# M7075X.net
KiCad netlist of a schematic drawn in EAGLE
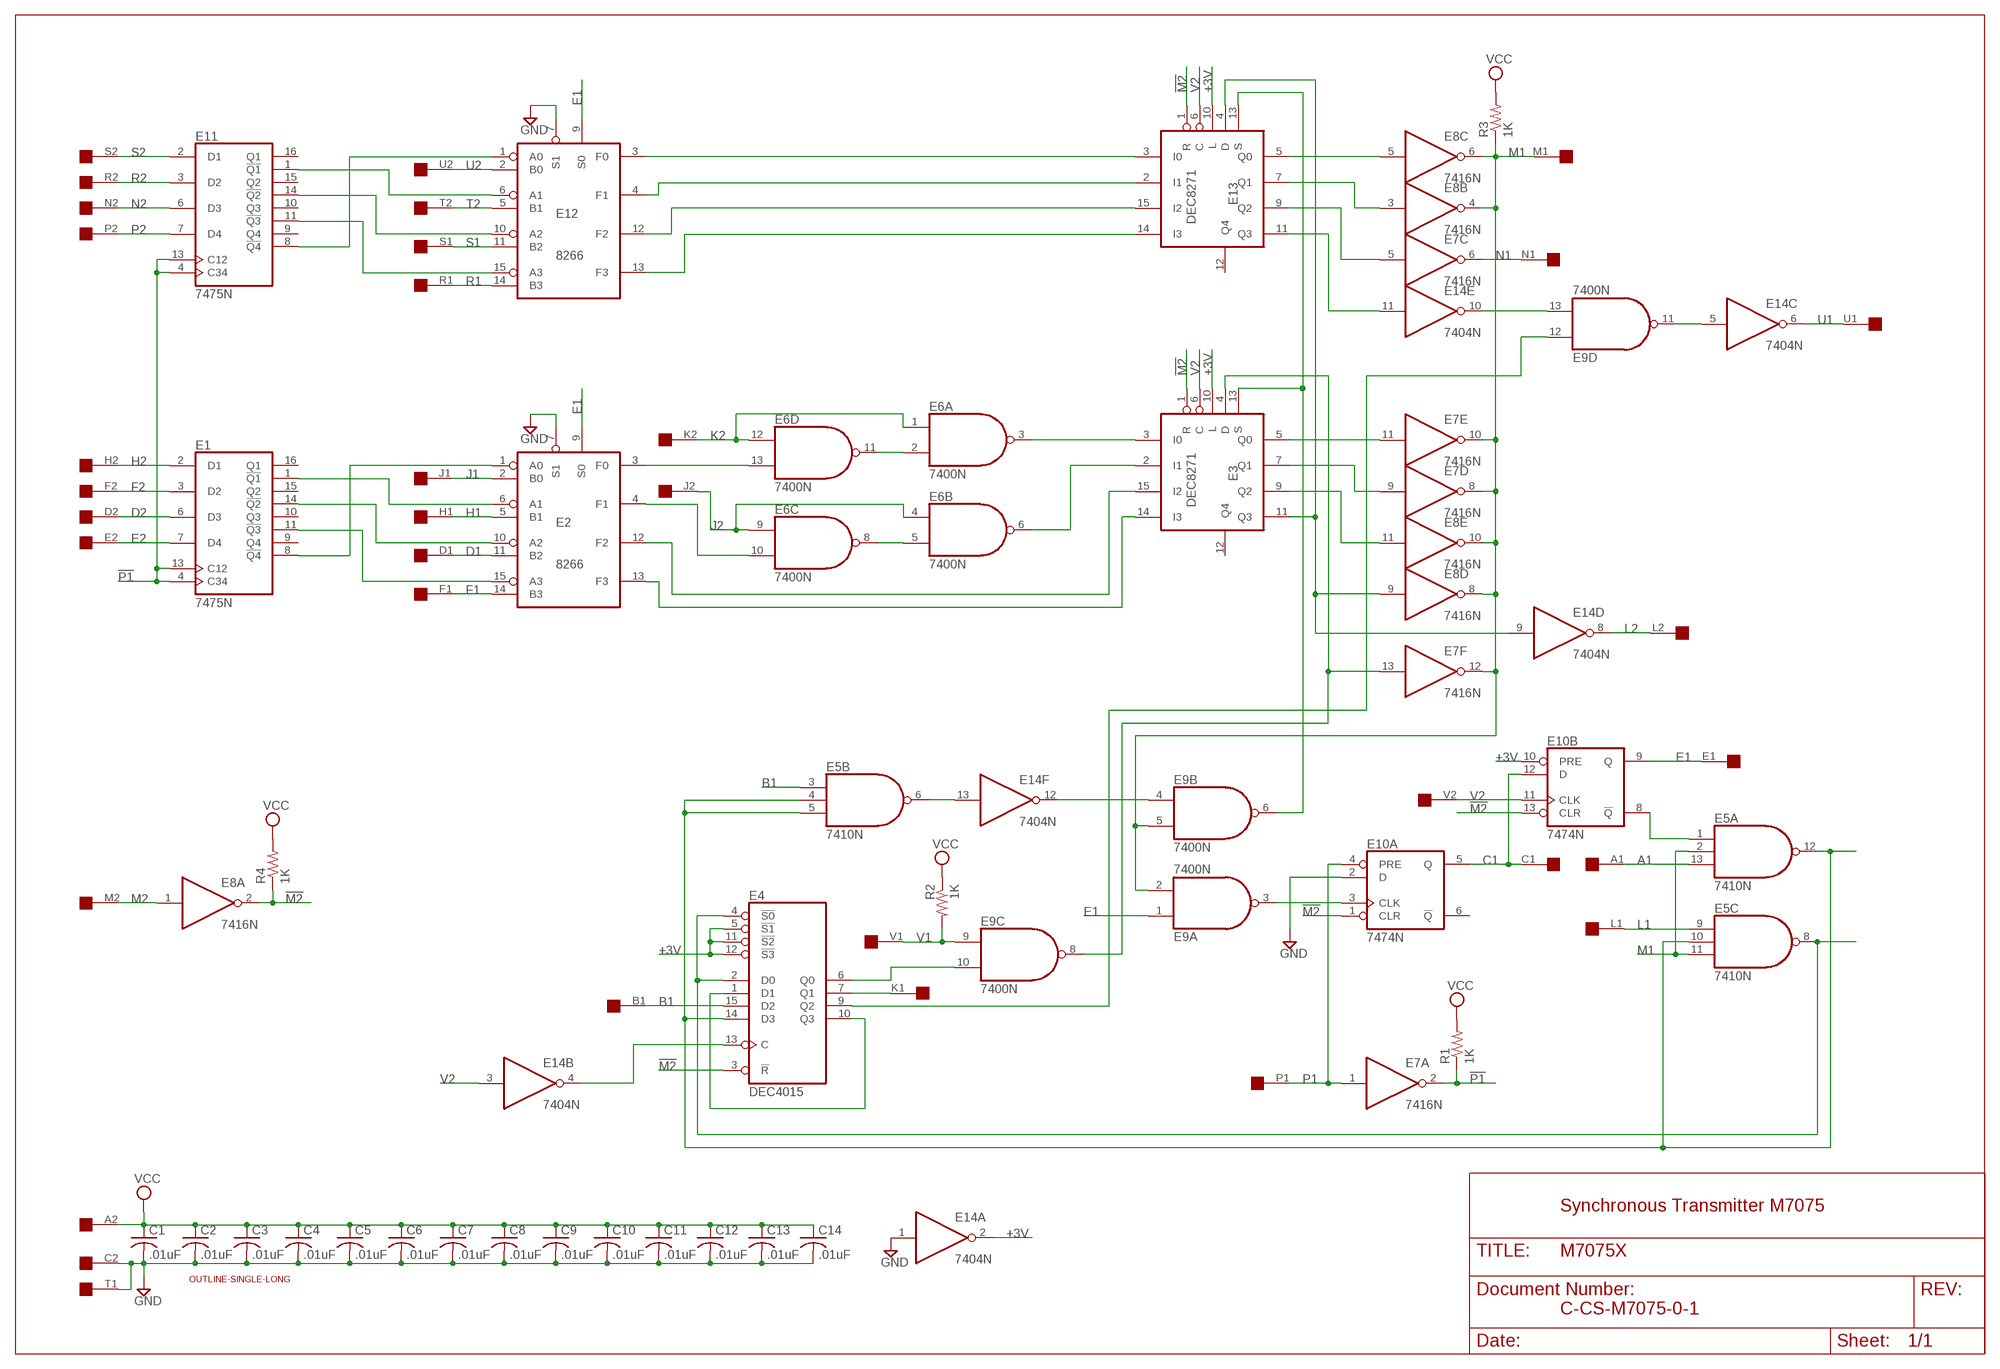
[diagram p0: schematic, sheet 1]

(export (version "E")
  (design (tool "Eeschema 10.0.6"))
  (components
    (comp (ref "C1")
      (value ".01uF")
      (footprint "eagle-import:C050-025X075")
      (libsource (lib "eagle-import") (part "C-US050-025X075"))
    )
    (comp (ref "C2")
      (value ".01uF")
      (footprint "eagle-import:C050-025X075")
      (libsource (lib "eagle-import") (part "C-US050-025X075"))
    )
    (comp (ref "C3")
      (value ".01uF")
      (footprint "eagle-import:C050-025X075")
      (libsource (lib "eagle-import") (part "C-US050-025X075"))
    )
    (comp (ref "C4")
      (value ".01uF")
      (footprint "eagle-import:C050-025X075")
      (libsource (lib "eagle-import") (part "C-US050-025X075"))
    )
    (comp (ref "C5")
      (value ".01uF")
      (footprint "eagle-import:C050-025X075")
      (libsource (lib "eagle-import") (part "C-US050-025X075"))
    )
    (comp (ref "C6")
      (value ".01uF")
      (footprint "eagle-import:C050-025X075")
      (libsource (lib "eagle-import") (part "C-US050-025X075"))
    )
    (comp (ref "C7")
      (value ".01uF")
      (footprint "eagle-import:C050-025X075")
      (libsource (lib "eagle-import") (part "C-US050-025X075"))
    )
    (comp (ref "C8")
      (value ".01uF")
      (footprint "eagle-import:C050-025X075")
      (libsource (lib "eagle-import") (part "C-US050-025X075"))
    )
    (comp (ref "C9")
      (value ".01uF")
      (footprint "eagle-import:C050-025X075")
      (libsource (lib "eagle-import") (part "C-US050-025X075"))
    )
    (comp (ref "C10")
      (value ".01uF")
      (footprint "eagle-import:C050-025X075")
      (libsource (lib "eagle-import") (part "C-US050-025X075"))
    )
    (comp (ref "C11")
      (value ".01uF")
      (footprint "eagle-import:C050-025X075")
      (libsource (lib "eagle-import") (part "C-US050-025X075"))
    )
    (comp (ref "C12")
      (value ".01uF")
      (footprint "eagle-import:C050-025X075")
      (libsource (lib "eagle-import") (part "C-US050-025X075"))
    )
    (comp (ref "C13")
      (value ".01uF")
      (footprint "eagle-import:C050-025X075")
      (libsource (lib "eagle-import") (part "C-US050-025X075"))
    )
    (comp (ref "C14")
      (value ".01uF")
      (footprint "eagle-import:C050-025X075")
      (libsource (lib "eagle-import") (part "C-US050-025X075"))
    )
    (comp (ref "E1")
      (value "7475N")
      (footprint "eagle-import:DIL16")
      (libsource (lib "eagle-import") (part "7475N"))
    )
    (comp (ref "E2")
      (value "8266")
      (footprint "eagle-import:DIL16")
      (libsource (lib "eagle-import") (part "8266"))
    )
    (comp (ref "E3")
      (value "DEC8271")
      (footprint "eagle-import:DIL16")
      (libsource (lib "eagle-import") (part "DEC8271"))
    )
    (comp (ref "E4")
      (value "DEC4015")
      (footprint "eagle-import:DIL16")
      (libsource (lib "eagle-import") (part "DEC4015"))
    )
    (comp (ref "E5")
      (value "7410N")
      (footprint "eagle-import:DIL14")
      (libsource (lib "eagle-import") (part "7410N"))
    )
    (comp (ref "E6")
      (value "7400N")
      (footprint "eagle-import:DIL14")
      (libsource (lib "eagle-import") (part "7400N"))
    )
    (comp (ref "E7")
      (value "7416N")
      (footprint "eagle-import:DIL14")
      (libsource (lib "eagle-import") (part "7416N"))
    )
    (comp (ref "E8")
      (value "7416N")
      (footprint "eagle-import:DIL14")
      (libsource (lib "eagle-import") (part "7416N"))
    )
    (comp (ref "E9")
      (value "7400N")
      (footprint "eagle-import:DIL14")
      (libsource (lib "eagle-import") (part "7400N"))
    )
    (comp (ref "E10")
      (value "7474N")
      (footprint "eagle-import:DIL14")
      (libsource (lib "eagle-import") (part "7474NS"))
    )
    (comp (ref "E11")
      (value "7475N")
      (footprint "eagle-import:DIL16")
      (libsource (lib "eagle-import") (part "7475N"))
    )
    (comp (ref "E12")
      (value "8266")
      (footprint "eagle-import:DIL16")
      (libsource (lib "eagle-import") (part "8266"))
    )
    (comp (ref "E13")
      (value "DEC8271")
      (footprint "eagle-import:DIL16")
      (libsource (lib "eagle-import") (part "DEC8271"))
    )
    (comp (ref "E14")
      (value "7404N")
      (footprint "eagle-import:DIL14")
      (libsource (lib "eagle-import") (part "7404N"))
    )
    (comp (ref "R1")
      (value "1K")
      (footprint "eagle-import:0207_10")
      (libsource (lib "eagle-import") (part "R-US_0207/10"))
    )
    (comp (ref "R2")
      (value "1K")
      (footprint "eagle-import:0207_10")
      (libsource (lib "eagle-import") (part "R-US_0207/10"))
    )
    (comp (ref "R3")
      (value "1K")
      (footprint "eagle-import:0207_10")
      (libsource (lib "eagle-import") (part "R-US_0207/10"))
    )
    (comp (ref "R4")
      (value "1K")
      (footprint "eagle-import:0207_10")
      (libsource (lib "eagle-import") (part "R-US_0207/10"))
    )
    (comp (ref "U$1")
      (value "OUTLINE-SINGLE-LONG")
      (footprint "eagle-import:SINGLE-LONG")
      (libsource (lib "eagle-import") (part "OUTLINE-SINGLE-LONG"))
    )
    (comp (ref "U$2")
      (value "SINGLE")
      (footprint "eagle-import:EDGE-CON2")
      (libsource (lib "eagle-import") (part "SINGLE"))
    )
  )
  (nets
    (net (code "1") (name "/+3V") (class "Default")
      (node (ref "E10") (pin "10") (pinfunction "PRE_10") (pintype "input"))
      (node (ref "E13") (pin "10") (pinfunction "L_10") (pintype "input"))
      (node (ref "E14") (pin "2") (pinfunction "O_2") (pintype "output"))
      (node (ref "E3") (pin "10") (pinfunction "L_10") (pintype "input"))
      (node (ref "E4") (pin "11") (pinfunction "~{S2}_11") (pintype "input"))
      (node (ref "E4") (pin "12") (pinfunction "~{S3}_12") (pintype "input"))
      (node (ref "E4") (pin "5") (pinfunction "~{S1}_5") (pintype "input"))
    )
    (net (code "2") (name "/A1") (class "Default")
      (node (ref "E5") (pin "13") (pinfunction "I2_13") (pintype "input"))
      (node (ref "U$2") (pin "A1") (pinfunction "1_A1") (pintype "bidirectional"))
    )
    (net (code "3") (name "/B1") (class "Default")
      (node (ref "E4") (pin "15") (pinfunction "D2_15") (pintype "input"))
      (node (ref "E5") (pin "3") (pinfunction "I0_3") (pintype "input"))
      (node (ref "U$2") (pin "B1") (pinfunction "1_B1") (pintype "bidirectional"))
    )
    (net (code "4") (name "/C1") (class "Default")
      (node (ref "E10") (pin "12") (pinfunction "D_12") (pintype "input"))
      (node (ref "E10") (pin "5") (pinfunction "Q_5") (pintype "output"))
      (node (ref "U$2") (pin "C1") (pinfunction "1_C1") (pintype "bidirectional"))
    )
    (net (code "5") (name "/D1") (class "Default")
      (node (ref "E2") (pin "11") (pinfunction "B2_11") (pintype "input"))
      (node (ref "U$2") (pin "D1") (pinfunction "1_D1") (pintype "bidirectional"))
    )
    (net (code "6") (name "/D2") (class "Default")
      (node (ref "E1") (pin "6") (pinfunction "D3_6") (pintype "input"))
      (node (ref "U$2") (pin "D2") (pinfunction "1_D2") (pintype "bidirectional"))
    )
    (net (code "7") (name "/E1") (class "Default")
      (node (ref "E10") (pin "9") (pinfunction "Q_9") (pintype "output"))
      (node (ref "E12") (pin "9") (pinfunction "S0_9") (pintype "input"))
      (node (ref "E2") (pin "9") (pinfunction "S0_9") (pintype "input"))
      (node (ref "E9") (pin "1") (pinfunction "I0_1") (pintype "input"))
      (node (ref "U$2") (pin "E1") (pinfunction "1_E1") (pintype "bidirectional"))
    )
    (net (code "8") (name "/E2") (class "Default")
      (node (ref "E1") (pin "7") (pinfunction "D4_7") (pintype "input"))
      (node (ref "U$2") (pin "E2") (pinfunction "1_E2") (pintype "bidirectional"))
    )
    (net (code "9") (name "/F1") (class "Default")
      (node (ref "E2") (pin "14") (pinfunction "B3_14") (pintype "input"))
      (node (ref "U$2") (pin "F1") (pinfunction "1_F1") (pintype "bidirectional"))
    )
    (net (code "10") (name "/F2") (class "Default")
      (node (ref "E1") (pin "3") (pinfunction "D2_3") (pintype "input"))
      (node (ref "U$2") (pin "F2") (pinfunction "1_F2") (pintype "bidirectional"))
    )
    (net (code "11") (name "/H1") (class "Default")
      (node (ref "E2") (pin "5") (pinfunction "B1_5") (pintype "input"))
      (node (ref "U$2") (pin "H1") (pinfunction "1_H1") (pintype "bidirectional"))
    )
    (net (code "12") (name "/H2") (class "Default")
      (node (ref "E1") (pin "2") (pinfunction "D1_2") (pintype "input"))
      (node (ref "U$2") (pin "H2") (pinfunction "1_H2") (pintype "bidirectional"))
    )
    (net (code "13") (name "/J1") (class "Default")
      (node (ref "E2") (pin "2") (pinfunction "B0_2") (pintype "input"))
      (node (ref "U$2") (pin "J1") (pinfunction "1_J1") (pintype "bidirectional"))
    )
    (net (code "14") (name "/J2") (class "Default")
      (node (ref "E6") (pin "4") (pinfunction "I0_4") (pintype "input"))
      (node (ref "E6") (pin "9") (pinfunction "I0_9") (pintype "input"))
      (node (ref "U$2") (pin "J2") (pinfunction "1_J2") (pintype "bidirectional"))
    )
    (net (code "15") (name "/K2") (class "Default")
      (node (ref "E6") (pin "1") (pinfunction "I0_1") (pintype "input"))
      (node (ref "E6") (pin "12") (pinfunction "I0_12") (pintype "input"))
      (node (ref "U$2") (pin "K2") (pinfunction "1_K2") (pintype "bidirectional"))
    )
    (net (code "16") (name "/L1") (class "Default")
      (node (ref "E5") (pin "9") (pinfunction "I0_9") (pintype "input"))
      (node (ref "U$2") (pin "L1") (pinfunction "1_L1") (pintype "bidirectional"))
    )
    (net (code "17") (name "/L2") (class "Default")
      (node (ref "E14") (pin "8") (pinfunction "O_8") (pintype "output"))
      (node (ref "U$2") (pin "L2") (pinfunction "1_L2") (pintype "bidirectional"))
    )
    (net (code "18") (name "/M1") (class "Default")
      (node (ref "E5") (pin "11") (pinfunction "I2_11") (pintype "input"))
      (node (ref "E5") (pin "2") (pinfunction "I1_2") (pintype "input"))
      (node (ref "E7") (pin "10") (pinfunction "O_10") (pintype "open_collector"))
      (node (ref "E7") (pin "12") (pinfunction "O_12") (pintype "open_collector"))
      (node (ref "E7") (pin "8") (pinfunction "O_8") (pintype "open_collector"))
      (node (ref "E8") (pin "10") (pinfunction "O_10") (pintype "open_collector"))
      (node (ref "E8") (pin "4") (pinfunction "O_4") (pintype "open_collector"))
      (node (ref "E8") (pin "6") (pinfunction "O_6") (pintype "open_collector"))
      (node (ref "E8") (pin "8") (pinfunction "O_8") (pintype "open_collector"))
      (node (ref "E9") (pin "2") (pinfunction "I1_2") (pintype "input"))
      (node (ref "E9") (pin "5") (pinfunction "I1_5") (pintype "input"))
      (node (ref "R3") (pin "1") (pinfunction "1_1") (pintype "passive"))
      (node (ref "U$2") (pin "M1") (pinfunction "1_M1") (pintype "bidirectional"))
    )
    (net (code "19") (name "/M2") (class "Default")
      (node (ref "E8") (pin "1") (pinfunction "I_1") (pintype "input"))
      (node (ref "U$2") (pin "M2") (pinfunction "1_M2") (pintype "bidirectional"))
    )
    (net (code "20") (name "/N1") (class "Default")
      (node (ref "E7") (pin "6") (pinfunction "O_6") (pintype "open_collector"))
      (node (ref "U$2") (pin "N1") (pinfunction "1_N1") (pintype "bidirectional"))
    )
    (net (code "21") (name "/N2") (class "Default")
      (node (ref "E11") (pin "6") (pinfunction "D3_6") (pintype "input"))
      (node (ref "U$2") (pin "N2") (pinfunction "1_N2") (pintype "bidirectional"))
    )
    (net (code "22") (name "/P1") (class "Default")
      (node (ref "E10") (pin "4") (pinfunction "PRE_4") (pintype "input"))
      (node (ref "E7") (pin "1") (pinfunction "I_1") (pintype "input"))
      (node (ref "U$2") (pin "P1") (pinfunction "1_P1") (pintype "bidirectional"))
    )
    (net (code "23") (name "/P2") (class "Default")
      (node (ref "E11") (pin "7") (pinfunction "D4_7") (pintype "input"))
      (node (ref "U$2") (pin "P2") (pinfunction "1_P2") (pintype "bidirectional"))
    )
    (net (code "24") (name "/R1") (class "Default")
      (node (ref "E12") (pin "14") (pinfunction "B3_14") (pintype "input"))
      (node (ref "U$2") (pin "R1") (pinfunction "1_R1") (pintype "bidirectional"))
    )
    (net (code "25") (name "/R2") (class "Default")
      (node (ref "E11") (pin "3") (pinfunction "D2_3") (pintype "input"))
      (node (ref "U$2") (pin "R2") (pinfunction "1_R2") (pintype "bidirectional"))
    )
    (net (code "26") (name "/S1") (class "Default")
      (node (ref "E12") (pin "11") (pinfunction "B2_11") (pintype "input"))
      (node (ref "U$2") (pin "S1") (pinfunction "1_S1") (pintype "bidirectional"))
    )
    (net (code "27") (name "/S2") (class "Default")
      (node (ref "E11") (pin "2") (pinfunction "D1_2") (pintype "input"))
      (node (ref "U$2") (pin "S2") (pinfunction "1_S2") (pintype "bidirectional"))
    )
    (net (code "28") (name "/T2") (class "Default")
      (node (ref "E12") (pin "5") (pinfunction "B1_5") (pintype "input"))
      (node (ref "U$2") (pin "T2") (pinfunction "1_T2") (pintype "bidirectional"))
    )
    (net (code "29") (name "/U1") (class "Default")
      (node (ref "E14") (pin "6") (pinfunction "O_6") (pintype "output"))
      (node (ref "U$2") (pin "U1") (pinfunction "1_U1") (pintype "bidirectional"))
    )
    (net (code "30") (name "/U2") (class "Default")
      (node (ref "E12") (pin "2") (pinfunction "B0_2") (pintype "input"))
      (node (ref "U$2") (pin "U2") (pinfunction "1_U2") (pintype "bidirectional"))
    )
    (net (code "31") (name "/V1") (class "Default")
      (node (ref "E9") (pin "9") (pinfunction "I0_9") (pintype "input"))
      (node (ref "R2") (pin "2") (pinfunction "2_2") (pintype "passive"))
      (node (ref "U$2") (pin "V1") (pinfunction "1_V1") (pintype "bidirectional"))
    )
    (net (code "32") (name "/V2") (class "Default")
      (node (ref "E10") (pin "11") (pinfunction "CLK_11") (pintype "input"))
      (node (ref "E13") (pin "6") (pinfunction "C_6") (pintype "input"))
      (node (ref "E14") (pin "3") (pinfunction "I_3") (pintype "input"))
      (node (ref "E3") (pin "6") (pinfunction "C_6") (pintype "input"))
      (node (ref "U$2") (pin "V2") (pinfunction "1_V2") (pintype "bidirectional"))
    )
    (net (code "33") (name "/~{M2}") (class "Default")
      (node (ref "E10") (pin "1") (pinfunction "CLR_1") (pintype "input"))
      (node (ref "E10") (pin "13") (pinfunction "CLR_13") (pintype "input"))
      (node (ref "E13") (pin "1") (pinfunction "R_1") (pintype "input"))
      (node (ref "E3") (pin "1") (pinfunction "R_1") (pintype "input"))
      (node (ref "E4") (pin "3") (pinfunction "~{R}_3") (pintype "input"))
      (node (ref "E8") (pin "2") (pinfunction "O_2") (pintype "open_collector"))
      (node (ref "R4") (pin "1") (pinfunction "1_1") (pintype "passive"))
    )
    (net (code "34") (name "/~{P1}") (class "Default")
      (node (ref "E1") (pin "13") (pinfunction "C12_13") (pintype "input"))
      (node (ref "E1") (pin "4") (pinfunction "C34_4") (pintype "input"))
      (node (ref "E11") (pin "13") (pinfunction "C12_13") (pintype "input"))
      (node (ref "E11") (pin "4") (pinfunction "C34_4") (pintype "input"))
      (node (ref "E7") (pin "2") (pinfunction "O_2") (pintype "open_collector"))
      (node (ref "R1") (pin "1") (pinfunction "1_1") (pintype "passive"))
    )
    (net (code "35") (name "GND") (class "Default")
      (node (ref "C1") (pin "2") (pinfunction "2_2") (pintype "passive"))
      (node (ref "C10") (pin "2") (pinfunction "2_2") (pintype "passive"))
      (node (ref "C11") (pin "2") (pinfunction "2_2") (pintype "passive"))
      (node (ref "C12") (pin "2") (pinfunction "2_2") (pintype "passive"))
      (node (ref "C13") (pin "2") (pinfunction "2_2") (pintype "passive"))
      (node (ref "C14") (pin "2") (pinfunction "2_2") (pintype "passive"))
      (node (ref "C2") (pin "2") (pinfunction "2_2") (pintype "passive"))
      (node (ref "C3") (pin "2") (pinfunction "2_2") (pintype "passive"))
      (node (ref "C4") (pin "2") (pinfunction "2_2") (pintype "passive"))
      (node (ref "C5") (pin "2") (pinfunction "2_2") (pintype "passive"))
      (node (ref "C6") (pin "2") (pinfunction "2_2") (pintype "passive"))
      (node (ref "C7") (pin "2") (pinfunction "2_2") (pintype "passive"))
      (node (ref "C8") (pin "2") (pinfunction "2_2") (pintype "passive"))
      (node (ref "C9") (pin "2") (pinfunction "2_2") (pintype "passive"))
      (node (ref "E10") (pin "2") (pinfunction "D_2") (pintype "input"))
      (node (ref "E12") (pin "7") (pinfunction "S1_7") (pintype "input"))
      (node (ref "E14") (pin "1") (pinfunction "I_1") (pintype "input"))
      (node (ref "E2") (pin "7") (pinfunction "S1_7") (pintype "input"))
      (node (ref "U$2") (pin "C2") (pinfunction "1_C2") (pintype "bidirectional"))
      (node (ref "U$2") (pin "T1") (pinfunction "1_T1") (pintype "bidirectional"))
    )
    (net (code "36") (name "Net-(E1A-~{Q1})") (class "Default")
      (node (ref "E1") (pin "1") (pinfunction "~{Q1}_1") (pintype "output"))
      (node (ref "E2") (pin "6") (pinfunction "A1_6") (pintype "input"))
    )
    (net (code "37") (name "Net-(E1A-~{Q2})") (class "Default")
      (node (ref "E1") (pin "14") (pinfunction "~{Q2}_14") (pintype "output"))
      (node (ref "E2") (pin "10") (pinfunction "A2_10") (pintype "input"))
    )
    (net (code "38") (name "Net-(E1A-~{Q3})") (class "Default")
      (node (ref "E1") (pin "11") (pinfunction "~{Q3}_11") (pintype "output"))
      (node (ref "E2") (pin "15") (pinfunction "A3_15") (pintype "input"))
    )
    (net (code "39") (name "Net-(E1A-~{Q4})") (class "Default")
      (node (ref "E1") (pin "8") (pinfunction "~{Q4}_8") (pintype "output"))
      (node (ref "E2") (pin "1") (pinfunction "A0_1") (pintype "input"))
    )
    (net (code "40") (name "Net-(E2A-F0)") (class "Default")
      (node (ref "E2") (pin "3") (pinfunction "F0_3") (pintype "output"))
      (node (ref "E6") (pin "13") (pinfunction "I1_13") (pintype "input"))
    )
    (net (code "41") (name "Net-(E2A-F1)") (class "Default")
      (node (ref "E2") (pin "4") (pinfunction "F1_4") (pintype "output"))
      (node (ref "E6") (pin "10") (pinfunction "I1_10") (pintype "input"))
    )
    (net (code "42") (name "Net-(E2A-F2)") (class "Default")
      (node (ref "E2") (pin "12") (pinfunction "F2_12") (pintype "output"))
      (node (ref "E3") (pin "15") (pinfunction "I2_15") (pintype "input"))
    )
    (net (code "43") (name "Net-(E2A-F3)") (class "Default")
      (node (ref "E2") (pin "13") (pinfunction "F3_13") (pintype "output"))
      (node (ref "E3") (pin "14") (pinfunction "I3_14") (pintype "input"))
    )
    (net (code "44") (name "Net-(E3A-D)") (class "Default")
      (node (ref "E3") (pin "4") (pinfunction "D_4") (pintype "input"))
      (node (ref "E7") (pin "13") (pinfunction "I_13") (pintype "input"))
      (node (ref "E9") (pin "8") (pinfunction "O_8") (pintype "output"))
    )
    (net (code "45") (name "Net-(E3A-I0)") (class "Default")
      (node (ref "E3") (pin "3") (pinfunction "I0_3") (pintype "input"))
      (node (ref "E6") (pin "3") (pinfunction "O_3") (pintype "output"))
    )
    (net (code "46") (name "Net-(E3A-I1)") (class "Default")
      (node (ref "E3") (pin "2") (pinfunction "I1_2") (pintype "input"))
      (node (ref "E6") (pin "6") (pinfunction "O_6") (pintype "output"))
    )
    (net (code "47") (name "Net-(E3A-Q0)") (class "Default")
      (node (ref "E3") (pin "5") (pinfunction "Q0_5") (pintype "output"))
      (node (ref "E7") (pin "11") (pinfunction "I_11") (pintype "input"))
    )
    (net (code "48") (name "Net-(E3A-Q1)") (class "Default")
      (node (ref "E3") (pin "7") (pinfunction "Q1_7") (pintype "output"))
      (node (ref "E7") (pin "9") (pinfunction "I_9") (pintype "input"))
    )
    (net (code "49") (name "Net-(E3A-Q2)") (class "Default")
      (node (ref "E3") (pin "9") (pinfunction "Q2_9") (pintype "output"))
      (node (ref "E8") (pin "11") (pinfunction "I_11") (pintype "input"))
    )
    (net (code "50") (name "Net-(E4A-D0)") (class "Default")
      (node (ref "E4") (pin "2") (pinfunction "D0_2") (pintype "input"))
      (node (ref "E4") (pin "4") (pinfunction "~{S0}_4") (pintype "input"))
      (node (ref "E5") (pin "8") (pinfunction "O_8") (pintype "output"))
    )
    (net (code "51") (name "Net-(E4A-D1)") (class "Default")
      (node (ref "E4") (pin "1") (pinfunction "D1_1") (pintype "input"))
      (node (ref "E4") (pin "10") (pinfunction "Q3_10") (pintype "output"))
    )
    (net (code "52") (name "Net-(E4A-D3)") (class "Default")
      (node (ref "E4") (pin "14") (pinfunction "D3_14") (pintype "input"))
      (node (ref "E5") (pin "10") (pinfunction "I1_10") (pintype "input"))
      (node (ref "E5") (pin "12") (pinfunction "O_12") (pintype "output"))
      (node (ref "E5") (pin "4") (pinfunction "I1_4") (pintype "input"))
      (node (ref "E5") (pin "5") (pinfunction "I2_5") (pintype "input"))
    )
    (net (code "53") (name "Net-(E4A-Q0)") (class "Default")
      (node (ref "E4") (pin "6") (pinfunction "Q0_6") (pintype "output"))
      (node (ref "E9") (pin "10") (pinfunction "I1_10") (pintype "input"))
    )
    (net (code "54") (name "Net-(E4A-Q1)") (class "Default")
      (node (ref "E4") (pin "7") (pinfunction "Q1_7") (pintype "output"))
      (node (ref "U$2") (pin "K1") (pinfunction "1_K1") (pintype "bidirectional"))
    )
    (net (code "55") (name "Net-(E4A-Q2)") (class "Default")
      (node (ref "E4") (pin "9") (pinfunction "Q2_9") (pintype "output"))
      (node (ref "E9") (pin "12") (pinfunction "I0_12") (pintype "input"))
    )
    (net (code "56") (name "Net-(E6A-I1)") (class "Default")
      (node (ref "E6") (pin "11") (pinfunction "O_11") (pintype "output"))
      (node (ref "E6") (pin "2") (pinfunction "I1_2") (pintype "input"))
    )
    (net (code "57") (name "Net-(E6B-I1)") (class "Default")
      (node (ref "E6") (pin "5") (pinfunction "I1_5") (pintype "input"))
      (node (ref "E6") (pin "8") (pinfunction "O_8") (pintype "output"))
    )
    (net (code "58") (name "Net-(E10A-CLK)") (class "Default")
      (node (ref "E10") (pin "3") (pinfunction "CLK_3") (pintype "input"))
      (node (ref "E9") (pin "3") (pinfunction "O_3") (pintype "output"))
    )
    (net (code "59") (name "Net-(E10B-~{Q})") (class "Default")
      (node (ref "E10") (pin "8") (pinfunction "~{Q}_8") (pintype "output"))
      (node (ref "E5") (pin "1") (pinfunction "I0_1") (pintype "input"))
    )
    (net (code "60") (name "Net-(E11A-~{Q1})") (class "Default")
      (node (ref "E11") (pin "1") (pinfunction "~{Q1}_1") (pintype "output"))
      (node (ref "E12") (pin "6") (pinfunction "A1_6") (pintype "input"))
    )
    (net (code "61") (name "Net-(E11A-~{Q2})") (class "Default")
      (node (ref "E11") (pin "14") (pinfunction "~{Q2}_14") (pintype "output"))
      (node (ref "E12") (pin "10") (pinfunction "A2_10") (pintype "input"))
    )
    (net (code "62") (name "Net-(E11A-~{Q3})") (class "Default")
      (node (ref "E11") (pin "11") (pinfunction "~{Q3}_11") (pintype "output"))
      (node (ref "E12") (pin "15") (pinfunction "A3_15") (pintype "input"))
    )
    (net (code "63") (name "Net-(E11A-~{Q4})") (class "Default")
      (node (ref "E11") (pin "8") (pinfunction "~{Q4}_8") (pintype "output"))
      (node (ref "E12") (pin "1") (pinfunction "A0_1") (pintype "input"))
    )
    (net (code "64") (name "Net-(E12A-F0)") (class "Default")
      (node (ref "E12") (pin "3") (pinfunction "F0_3") (pintype "output"))
      (node (ref "E13") (pin "3") (pinfunction "I0_3") (pintype "input"))
    )
    (net (code "65") (name "Net-(E12A-F1)") (class "Default")
      (node (ref "E12") (pin "4") (pinfunction "F1_4") (pintype "output"))
      (node (ref "E13") (pin "2") (pinfunction "I1_2") (pintype "input"))
    )
    (net (code "66") (name "Net-(E12A-F2)") (class "Default")
      (node (ref "E12") (pin "12") (pinfunction "F2_12") (pintype "output"))
      (node (ref "E13") (pin "15") (pinfunction "I2_15") (pintype "input"))
    )
    (net (code "67") (name "Net-(E12A-F3)") (class "Default")
      (node (ref "E12") (pin "13") (pinfunction "F3_13") (pintype "output"))
      (node (ref "E13") (pin "14") (pinfunction "I3_14") (pintype "input"))
    )
    (net (code "68") (name "Net-(E13A-D)") (class "Default")
      (node (ref "E13") (pin "4") (pinfunction "D_4") (pintype "input"))
      (node (ref "E14") (pin "9") (pinfunction "I_9") (pintype "input"))
      (node (ref "E3") (pin "11") (pinfunction "Q3_11") (pintype "output"))
      (node (ref "E8") (pin "9") (pinfunction "I_9") (pintype "input"))
    )
    (net (code "69") (name "Net-(E13A-Q0)") (class "Default")
      (node (ref "E13") (pin "5") (pinfunction "Q0_5") (pintype "output"))
      (node (ref "E8") (pin "5") (pinfunction "I_5") (pintype "input"))
    )
    (net (code "70") (name "Net-(E13A-Q1)") (class "Default")
      (node (ref "E13") (pin "7") (pinfunction "Q1_7") (pintype "output"))
      (node (ref "E8") (pin "3") (pinfunction "I_3") (pintype "input"))
    )
    (net (code "71") (name "Net-(E13A-Q2)") (class "Default")
      (node (ref "E13") (pin "9") (pinfunction "Q2_9") (pintype "output"))
      (node (ref "E7") (pin "5") (pinfunction "I_5") (pintype "input"))
    )
    (net (code "72") (name "Net-(E13A-Q3)") (class "Default")
      (node (ref "E13") (pin "11") (pinfunction "Q3_11") (pintype "output"))
      (node (ref "E14") (pin "11") (pinfunction "I_11") (pintype "input"))
    )
    (net (code "73") (name "Net-(E13A-S)") (class "Default")
      (node (ref "E13") (pin "13") (pinfunction "S_13") (pintype "input"))
      (node (ref "E3") (pin "13") (pinfunction "S_13") (pintype "input"))
      (node (ref "E9") (pin "6") (pinfunction "O_6") (pintype "output"))
    )
    (net (code "74") (name "Net-(E14B-O)") (class "Default")
      (node (ref "E14") (pin "4") (pinfunction "O_4") (pintype "output"))
      (node (ref "E4") (pin "13") (pinfunction "C_13") (pintype "bidirectional"))
    )
    (net (code "75") (name "Net-(E14C-I)") (class "Default")
      (node (ref "E14") (pin "5") (pinfunction "I_5") (pintype "input"))
      (node (ref "E9") (pin "11") (pinfunction "O_11") (pintype "output"))
    )
    (net (code "76") (name "Net-(E14E-O)") (class "Default")
      (node (ref "E14") (pin "10") (pinfunction "O_10") (pintype "output"))
      (node (ref "E9") (pin "13") (pinfunction "I1_13") (pintype "input"))
    )
    (net (code "77") (name "Net-(E14F-I)") (class "Default")
      (node (ref "E14") (pin "13") (pinfunction "I_13") (pintype "input"))
      (node (ref "E5") (pin "6") (pinfunction "O_6") (pintype "output"))
    )
    (net (code "78") (name "Net-(E14F-O)") (class "Default")
      (node (ref "E14") (pin "12") (pinfunction "O_12") (pintype "output"))
      (node (ref "E9") (pin "4") (pinfunction "I0_4") (pintype "input"))
    )
    (net (code "79") (name "VCC") (class "Default")
      (node (ref "C1") (pin "1") (pinfunction "1_1") (pintype "passive"))
      (node (ref "C10") (pin "1") (pinfunction "1_1") (pintype "passive"))
      (node (ref "C11") (pin "1") (pinfunction "1_1") (pintype "passive"))
      (node (ref "C12") (pin "1") (pinfunction "1_1") (pintype "passive"))
      (node (ref "C13") (pin "1") (pinfunction "1_1") (pintype "passive"))
      (node (ref "C14") (pin "1") (pinfunction "1_1") (pintype "passive"))
      (node (ref "C2") (pin "1") (pinfunction "1_1") (pintype "passive"))
      (node (ref "C3") (pin "1") (pinfunction "1_1") (pintype "passive"))
      (node (ref "C4") (pin "1") (pinfunction "1_1") (pintype "passive"))
      (node (ref "C5") (pin "1") (pinfunction "1_1") (pintype "passive"))
      (node (ref "C6") (pin "1") (pinfunction "1_1") (pintype "passive"))
      (node (ref "C7") (pin "1") (pinfunction "1_1") (pintype "passive"))
      (node (ref "C8") (pin "1") (pinfunction "1_1") (pintype "passive"))
      (node (ref "C9") (pin "1") (pinfunction "1_1") (pintype "passive"))
      (node (ref "R1") (pin "2") (pinfunction "2_2") (pintype "passive"))
      (node (ref "R2") (pin "1") (pinfunction "1_1") (pintype "passive"))
      (node (ref "R3") (pin "2") (pinfunction "2_2") (pintype "passive"))
      (node (ref "R4") (pin "2") (pinfunction "2_2") (pintype "passive"))
      (node (ref "U$2") (pin "A2") (pinfunction "1_A2") (pintype "bidirectional"))
    )
    (net (code "80") (name "unconnected-(E1A-Q1-Pad16)") (class "Default")
      (node (ref "E1") (pin "16") (pinfunction "Q1_16") (pintype "output"))
    )
    (net (code "81") (name "unconnected-(E1A-Q2-Pad15)") (class "Default")
      (node (ref "E1") (pin "15") (pinfunction "Q2_15") (pintype "output"))
    )
    (net (code "82") (name "unconnected-(E1A-Q3-Pad10)") (class "Default")
      (node (ref "E1") (pin "10") (pinfunction "Q3_10") (pintype "output"))
    )
    (net (code "83") (name "unconnected-(E1A-Q4-Pad9)") (class "Default")
      (node (ref "E1") (pin "9") (pinfunction "Q4_9") (pintype "output"))
    )
    (net (code "84") (name "unconnected-(E3A-Q4-Pad12)") (class "Default")
      (node (ref "E3") (pin "12") (pinfunction "Q4_12") (pintype "output"))
    )
    (net (code "85") (name "unconnected-(E10A-~{Q}-Pad6)") (class "Default")
      (node (ref "E10") (pin "6") (pinfunction "~{Q}_6") (pintype "output"))
    )
    (net (code "86") (name "unconnected-(E11A-Q1-Pad16)") (class "Default")
      (node (ref "E11") (pin "16") (pinfunction "Q1_16") (pintype "output"))
    )
    (net (code "87") (name "unconnected-(E11A-Q2-Pad15)") (class "Default")
      (node (ref "E11") (pin "15") (pinfunction "Q2_15") (pintype "output"))
    )
    (net (code "88") (name "unconnected-(E11A-Q3-Pad10)") (class "Default")
      (node (ref "E11") (pin "10") (pinfunction "Q3_10") (pintype "output"))
    )
    (net (code "89") (name "unconnected-(E11A-Q4-Pad9)") (class "Default")
      (node (ref "E11") (pin "9") (pinfunction "Q4_9") (pintype "output"))
    )
    (net (code "90") (name "unconnected-(E13A-Q4-Pad12)") (class "Default")
      (node (ref "E13") (pin "12") (pinfunction "Q4_12") (pintype "output"))
    )
  )
)
